# osi-brain.net
KiCad netlist of a schematic drawn in EAGLE
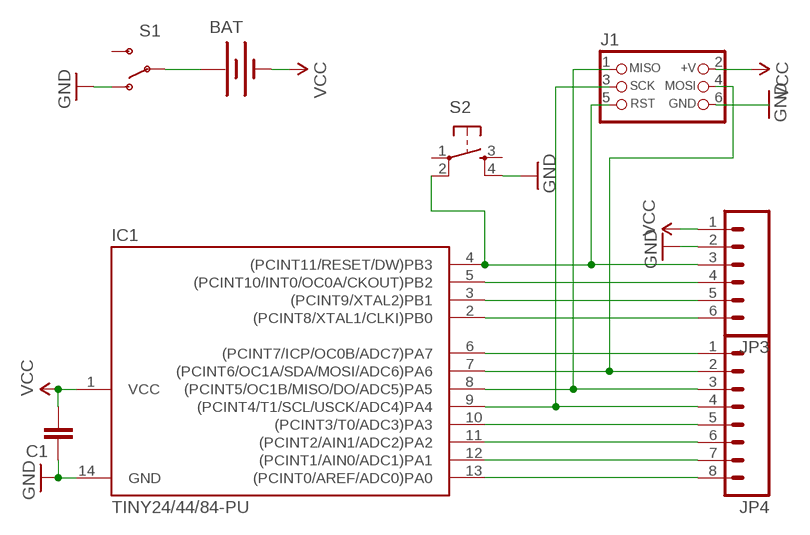
[diagram p0: schematic, sheet 1]

(export (version "E")
  (design (tool "Eeschema 10.0.6"))
  (components
    (comp (ref "BAT")
      (value "BATTERY20PTH")
      (footprint "eagle-import:BATTCOM_20MM_PTH")
      (libsource (lib "eagle-import") (part "BATTERY20PTH"))
    )
    (comp (ref "C1")
      (value "CAPKIT")
      (footprint "eagle-import:CAP-PTH-SMALL-KIT")
      (libsource (lib "eagle-import") (part "CAPKIT"))
    )
    (comp (ref "IC1")
      (value "TINY24/44/84-PU")
      (footprint "eagle-import:DIL14")
      (libsource (lib "eagle-import") (part "TINY24/44/84-PU"))
    )
    (comp (ref "J1")
      (value "CON_HEADER_PRG_AVR_ICSP-PTH")
      (footprint "eagle-import:HEADER_PRG_2X03")
      (libsource (lib "eagle-import") (part "CON_HEADER_PRG_AVR_ICSP-PTH"))
    )
    (comp (ref "JP3")
      (value "M06SIP")
      (footprint "eagle-import:1X06")
      (libsource (lib "eagle-import") (part "M06SIP"))
    )
    (comp (ref "JP4")
      (value "M081X08")
      (footprint "eagle-import:1X08")
      (libsource (lib "eagle-import") (part "M081X08"))
    )
    (comp (ref "S1")
      (value "SWITCH-SPSTPTH")
      (footprint "eagle-import:SWITCH-SPDT")
      (libsource (lib "eagle-import") (part "SWITCH-SPSTPTH"))
    )
    (comp (ref "S2")
      (value "TAC_SWITCHPTH")
      (footprint "eagle-import:TACTILE-PTH")
      (libsource (lib "eagle-import") (part "TAC_SWITCHPTH"))
    )
  )
  (nets
    (net (code "1") (name "GND") (class "Default")
      (node (ref "C1") (pin "1") (pinfunction "1_1") (pintype "passive"))
      (node (ref "IC1") (pin "14") (pinfunction "GND_14") (pintype "power_in"))
      (node (ref "JP3") (pin "2") (pinfunction "2_2") (pintype "passive"))
      (node (ref "S1") (pin "1") (pinfunction "O_1") (pintype "passive"))
      (node (ref "S2") (pin "4") (pinfunction "4_4") (pintype "passive"))
    )
    (net (code "2") (name "Net-(BAT-+)") (class "Default")
      (node (ref "BAT") (pin "1") (pinfunction "+_1") (pintype "power_in"))
      (node (ref "S1") (pin "2") (pinfunction "P_2") (pintype "passive"))
    )
    (net (code "3") (name "Net-(IC1-(PCINT0{slash}AREF{slash}ADC0)PA0)") (class "Default")
      (node (ref "IC1") (pin "13") (pinfunction "(PCINT0/AREF/ADC0)PA0_13") (pintype "bidirectional"))
      (node (ref "JP4") (pin "8") (pinfunction "8_8") (pintype "passive"))
    )
    (net (code "4") (name "Net-(IC1-(PCINT1{slash}AIN0{slash}ADC1)PA1)") (class "Default")
      (node (ref "IC1") (pin "12") (pinfunction "(PCINT1/AIN0/ADC1)PA1_12") (pintype "bidirectional"))
      (node (ref "JP4") (pin "7") (pinfunction "7_7") (pintype "passive"))
    )
    (net (code "5") (name "Net-(IC1-(PCINT2{slash}AIN1{slash}ADC2)PA2)") (class "Default")
      (node (ref "IC1") (pin "11") (pinfunction "(PCINT2/AIN1/ADC2)PA2_11") (pintype "bidirectional"))
      (node (ref "JP4") (pin "6") (pinfunction "6_6") (pintype "passive"))
    )
    (net (code "6") (name "Net-(IC1-(PCINT3{slash}T0{slash}ADC3)PA3)") (class "Default")
      (node (ref "IC1") (pin "10") (pinfunction "(PCINT3/T0/ADC3)PA3_10") (pintype "bidirectional"))
      (node (ref "JP4") (pin "5") (pinfunction "5_5") (pintype "passive"))
    )
    (net (code "7") (name "Net-(IC1-(PCINT4{slash}T1{slash}SCL{slash}USCK{slash}ADC4)PA4)") (class "Default")
      (node (ref "IC1") (pin "9") (pinfunction "(PCINT4/T1/SCL/USCK/ADC4)PA4_9") (pintype "bidirectional"))
      (node (ref "J1") (pin "3") (pinfunction "SCK_3") (pintype "passive"))
      (node (ref "JP4") (pin "4") (pinfunction "4_4") (pintype "passive"))
    )
    (net (code "8") (name "Net-(IC1-(PCINT5{slash}OC1B{slash}MISO{slash}DO{slash}ADC5)PA5)") (class "Default")
      (node (ref "IC1") (pin "8") (pinfunction "(PCINT5/OC1B/MISO/DO/ADC5)PA5_8") (pintype "bidirectional"))
      (node (ref "J1") (pin "1") (pinfunction "MISO_1") (pintype "passive"))
      (node (ref "JP4") (pin "3") (pinfunction "3_3") (pintype "passive"))
    )
    (net (code "9") (name "Net-(IC1-(PCINT6{slash}OC1A{slash}SDA{slash}MOSI{slash}ADC6)PA6)") (class "Default")
      (node (ref "IC1") (pin "7") (pinfunction "(PCINT6/OC1A/SDA/MOSI/ADC6)PA6_7") (pintype "bidirectional"))
      (node (ref "J1") (pin "4") (pinfunction "MOSI_4") (pintype "passive"))
      (node (ref "JP4") (pin "2") (pinfunction "2_2") (pintype "passive"))
    )
    (net (code "10") (name "Net-(IC1-(PCINT7{slash}ICP{slash}OC0B{slash}ADC7)PA7)") (class "Default")
      (node (ref "IC1") (pin "6") (pinfunction "(PCINT7/ICP/OC0B/ADC7)PA7_6") (pintype "bidirectional"))
      (node (ref "JP4") (pin "1") (pinfunction "1_1") (pintype "passive"))
    )
    (net (code "11") (name "Net-(IC1-(PCINT8{slash}XTAL1{slash}CLKI)PB0)") (class "Default")
      (node (ref "IC1") (pin "2") (pinfunction "(PCINT8/XTAL1/CLKI)PB0_2") (pintype "bidirectional"))
      (node (ref "JP3") (pin "6") (pinfunction "6_6") (pintype "passive"))
    )
    (net (code "12") (name "Net-(IC1-(PCINT9{slash}XTAL2)PB1)") (class "Default")
      (node (ref "IC1") (pin "3") (pinfunction "(PCINT9/XTAL2)PB1_3") (pintype "bidirectional"))
      (node (ref "JP3") (pin "5") (pinfunction "5_5") (pintype "passive"))
    )
    (net (code "13") (name "Net-(IC1-(PCINT10{slash}INT0{slash}OC0A{slash}CKOUT)PB2)") (class "Default")
      (node (ref "IC1") (pin "5") (pinfunction "(PCINT10/INT0/OC0A/CKOUT)PB2_5") (pintype "bidirectional"))
      (node (ref "JP3") (pin "4") (pinfunction "4_4") (pintype "passive"))
    )
    (net (code "14") (name "Net-(IC1-(PCINT11{slash}RESET{slash}DW)PB3)") (class "Default")
      (node (ref "IC1") (pin "4") (pinfunction "(PCINT11/RESET/DW)PB3_4") (pintype "bidirectional"))
      (node (ref "J1") (pin "5") (pinfunction "RST_5") (pintype "passive"))
      (node (ref "JP3") (pin "3") (pinfunction "3_3") (pintype "passive"))
      (node (ref "S2") (pin "2") (pinfunction "2_2") (pintype "passive"))
    )
    (net (code "15") (name "VCC") (class "Default")
      (node (ref "BAT") (pin "2") (pinfunction "-_2") (pintype "power_in"))
      (node (ref "C1") (pin "2") (pinfunction "2_2") (pintype "passive"))
      (node (ref "IC1") (pin "1") (pinfunction "VCC_1") (pintype "power_in"))
      (node (ref "J1") (pin "2") (pinfunction "+V_2") (pintype "passive"))
      (node (ref "JP3") (pin "1") (pinfunction "1_1") (pintype "passive"))
    )
    (net (code "16") (name "unconnected-(J1-GND-Pad6)") (class "Default")
      (node (ref "J1") (pin "6") (pinfunction "GND_6") (pintype "passive"))
    )
    (net (code "17") (name "unconnected-(S1-S-Pad3)") (class "Default")
      (node (ref "S1") (pin "3") (pinfunction "S_3") (pintype "passive"))
    )
    (net (code "18") (name "unconnected-(S2-Pad1)") (class "Default")
      (node (ref "S2") (pin "1") (pinfunction "1_1") (pintype "passive"))
    )
    (net (code "19") (name "unconnected-(S2-Pad3)") (class "Default")
      (node (ref "S2") (pin "3") (pinfunction "3_3") (pintype "passive"))
    )
  )
)
